# wristband2_ee459.net
KiCad netlist of a schematic drawn in Altium Designer
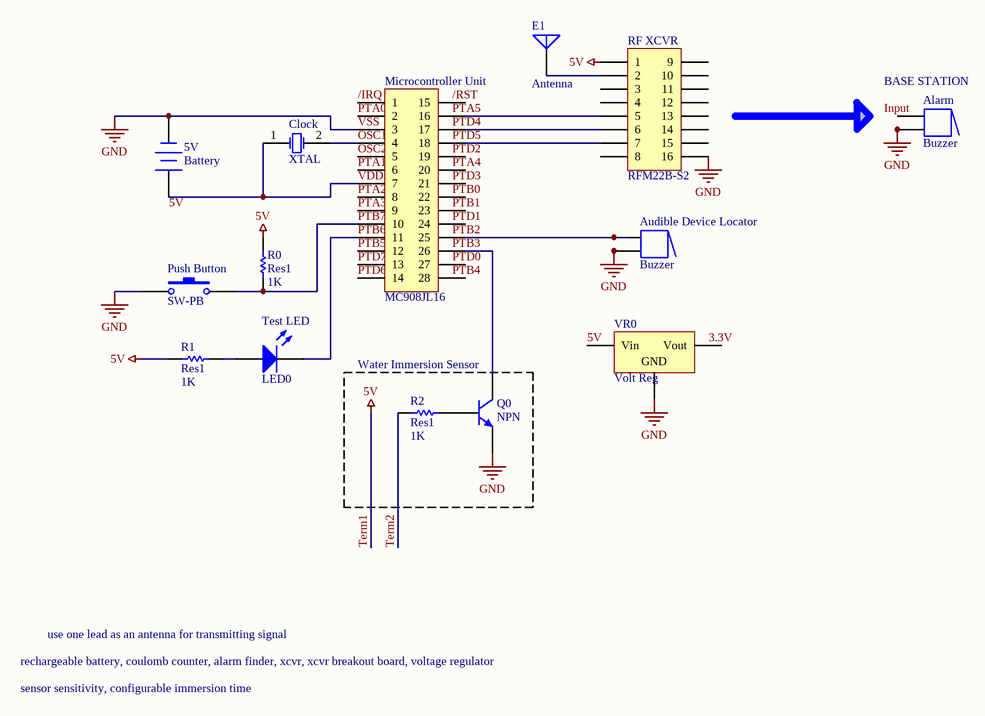
[diagram p0: wristband2_ee459.SchDoc]

(export (version "E")
  (design (tool "Eeschema 10.0.6"))
  (components
    (comp (ref "5V")
      (value "Battery")
      (footprint "BAT-2")
      (description "Multicell Battery")
      (fields (field (name "PUBLISHER") "Altium Limited"))
      (libsource (lib "Miscellaneous Devices") (part "Battery"))
    )
    (comp (ref "Alarm")
      (value "Buzzer")
      (footprint "ABSM-1574")
      (description "Magnetic Transducer Buzzer")
      (fields (field (name "PUBLISHER") "Altium Limited"))
      (libsource (lib "Miscellaneous Devices") (part "Buzzer"))
    )
    (comp (ref "Audible Device Locator")
      (value "Buzzer")
      (footprint "ABSM-1574")
      (description "Magnetic Transducer Buzzer")
      (fields (field (name "PUBLISHER") "Altium Limited"))
      (libsource (lib "Miscellaneous Devices") (part "Buzzer"))
    )
    (comp (ref "Clock")
      (value "XTAL")
      (footprint "R38")
      (description "Crystal Oscillator")
      (fields (field (name "PUBLISHER") "Altium Limited"))
      (libsource (lib "Miscellaneous Devices") (part "XTAL"))
    )
    (comp (ref "E1")
      (value "Antenna")
      (footprint "PIN1")
      (description "Generic Antenna")
      (fields (field (name "PUBLISHER") "Altium Limited"))
      (libsource (lib "Miscellaneous Devices") (part "Antenna"))
    )
    (comp (ref "Microcontroller Unit")
      (value "MC908JL16")
      (footprint "HDR2X14_CEN")
      (description "Header, 14-Pin, Dual row")
      (fields (field (name "PUBLISHER") "Altium Limited"))
      (libsource (lib "Miscellaneous Connectors") (part "Header 14X2A"))
    )
    (comp (ref "Push Button")
      (value "SW-PB")
      (footprint "SPST-2")
      (description "Switch")
      (fields (field (name "PUBLISHER") "Altium Limited"))
      (libsource (lib "Miscellaneous Devices") (part "SW-PB"))
    )
    (comp (ref "Q0")
      (value "NPN")
      (footprint "TO-226")
      (description "NPN Bipolar Transistor")
      (fields (field (name "PUBLISHER") "Altium Limited"))
      (libsource (lib "Miscellaneous Devices") (part "NPN"))
    )
    (comp (ref "R0")
      (value "Res1")
      (footprint "AXIAL-0.3")
      (description "Resistor")
      (fields (field (name "ALTIUM_VALUE") "1K") (field (name "PUBLISHER") "Altium Limited"))
      (libsource (lib "Miscellaneous Devices") (part "Res1"))
    )
    (comp (ref "R1")
      (value "Res1")
      (footprint "AXIAL-0.3")
      (description "Resistor")
      (fields (field (name "ALTIUM_VALUE") "1K") (field (name "PUBLISHER") "Altium Limited"))
      (libsource (lib "Miscellaneous Devices") (part "Res1"))
    )
    (comp (ref "R2")
      (value "Res1")
      (footprint "AXIAL-0.3")
      (description "Resistor")
      (fields (field (name "ALTIUM_VALUE") "1K") (field (name "PUBLISHER") "Altium Limited"))
      (libsource (lib "Miscellaneous Devices") (part "Res1"))
    )
    (comp (ref "RF XCVR")
      (value "RFM22B-S2")
      (footprint "HDR2X8_CEN")
      (description "Header, 8-Pin, Dual row")
      (fields (field (name "PUBLISHER") "Altium Limited"))
      (libsource (lib "Miscellaneous Connectors") (part "Header 8X2A"))
    )
    (comp (ref "Test LED")
      (value "LED0")
      (footprint "LED-0")
      (description "Typical INFRARED GaAs LED")
      (fields (field (name "PUBLISHER") "Altium Limited"))
      (libsource (lib "Miscellaneous Devices") (part "LED0"))
    )
    (comp (ref "VR0")
      (value "Volt Reg")
      (footprint "D2PAK")
      (description "Voltage Regulator")
      (fields (field (name "PUBLISHER") "Altium Limited"))
      (libsource (lib "Miscellaneous Devices") (part "Volt Reg"))
    )
  )
  (nets
    (net (code "3") (name "/OSC1") (class "Default")
      (node (ref "Clock") (pin "2") (pinfunction "OSC2_2") (pintype "passive"))
      (node (ref "Microcontroller Unit") (pin "4") (pinfunction "4_4") (pintype "passive"))
    )
    (net (code "4") (name "/OSC2") (class "Default")
      (node (ref "Microcontroller Unit") (pin "5") (pinfunction "5_5") (pintype "passive"))
    )
    (net (code "5") (name "/PTA0") (class "Default")
      (node (ref "Microcontroller Unit") (pin "2") (pinfunction "2_2") (pintype "passive"))
    )
    (net (code "6") (name "/PTA1") (class "Default")
      (node (ref "Microcontroller Unit") (pin "6") (pinfunction "6_6") (pintype "passive"))
    )
    (net (code "7") (name "/PTA2") (class "Default")
      (node (ref "Microcontroller Unit") (pin "8") (pinfunction "8_8") (pintype "passive"))
    )
    (net (code "8") (name "/PTA3") (class "Default")
      (node (ref "Microcontroller Unit") (pin "9") (pinfunction "9_9") (pintype "passive"))
    )
    (net (code "16") (name "/PTB5") (class "Default")
      (node (ref "Microcontroller Unit") (pin "12") (pinfunction "12_12") (pintype "passive"))
    )
    (net (code "17") (name "/PTB6") (class "Default")
      (node (ref "Microcontroller Unit") (pin "11") (pinfunction "11_11") (pintype "passive"))
      (node (ref "Test LED") (pin "2") (pinfunction "K_2") (pintype "passive"))
    )
    (net (code "18") (name "/PTB7") (class "Default")
      (node (ref "Microcontroller Unit") (pin "10") (pinfunction "10_10") (pintype "passive"))
      (node (ref "Push Button") (pin "2") (pinfunction "2_2") (pintype "passive"))
      (node (ref "R0") (pin "1") (pinfunction "1_1") (pintype "passive"))
    )
    (net (code "25") (name "/PTD6") (class "Default")
      (node (ref "Microcontroller Unit") (pin "14") (pinfunction "14_14") (pintype "passive"))
    )
    (net (code "26") (name "/PTD7") (class "Default")
      (node (ref "Microcontroller Unit") (pin "13") (pinfunction "13_13") (pintype "passive"))
    )
    (net (code "27") (name "/Term2") (class "Default")
      (node (ref "R2") (pin "1") (pinfunction "1_1") (pintype "passive"))
    )
    (net (code "28") (name "/VDD") (class "Default")
      (node (ref "5V") (pin "1") (pinfunction "+_1") (pintype "passive"))
      (node (ref "Clock") (pin "1") (pinfunction "OSC1_1") (pintype "passive"))
      (node (ref "Microcontroller Unit") (pin "7") (pinfunction "7_7") (pintype "passive"))
    )
    (net (code "29") (name "/{slash}IRQ") (class "Default")
      (node (ref "Microcontroller Unit") (pin "1") (pinfunction "1_1") (pintype "passive"))
    )
    (net (code "31") (name "5V") (class "Default")
      (node (ref "R0") (pin "2") (pinfunction "2_2") (pintype "passive"))
      (node (ref "R1") (pin "2") (pinfunction "2_2") (pintype "passive"))
      (node (ref "RF XCVR") (pin "1") (pinfunction "1_1") (pintype "passive"))
      (node (ref "VR0") (pin "1") (pinfunction "Vin_1") (pintype "passive"))
    )
    (net (code "32") (name "GND") (class "Default")
      (node (ref "5V") (pin "2") (pinfunction "-_2") (pintype "passive"))
      (node (ref "Alarm") (pin "2") (pinfunction "2_2") (pintype "passive"))
      (node (ref "Alarm") (pin "2A") (pinfunction "2A_2A") (pintype "passive"))
      (node (ref "Audible Device Locator") (pin "2") (pinfunction "2_2") (pintype "passive"))
      (node (ref "Audible Device Locator") (pin "2A") (pinfunction "2A_2A") (pintype "passive"))
      (node (ref "Microcontroller Unit") (pin "3") (pinfunction "3_3") (pintype "passive"))
      (node (ref "Push Button") (pin "1") (pinfunction "1_1") (pintype "passive"))
      (node (ref "Q0") (pin "3") (pinfunction "E_3") (pintype "passive"))
      (node (ref "RF XCVR") (pin "16") (pinfunction "16_16") (pintype "passive"))
      (node (ref "VR0") (pin "2") (pinfunction "GND_2") (pintype "passive"))
    )
    (net (code "33") (name "Net-(Alarm-Pad1)") (class "Default")
      (node (ref "Alarm") (pin "1") (pinfunction "1_1") (pintype "passive"))
      (node (ref "Alarm") (pin "1A") (pinfunction "1A_1A") (pintype "passive"))
    )
    (net (code "34") (name "Net-(Audible Device Locator-Pad1)") (class "Default")
      (node (ref "Audible Device Locator") (pin "1") (pinfunction "1_1") (pintype "passive"))
      (node (ref "Audible Device Locator") (pin "1A") (pinfunction "1A_1A") (pintype "passive"))
      (node (ref "Microcontroller Unit") (pin "25") (pinfunction "25_25") (pintype "passive"))
    )
    (net (code "35") (name "Net-(E1-A)") (class "Default")
      (node (ref "E1") (pin "1") (pinfunction "A_1") (pintype "passive"))
      (node (ref "RF XCVR") (pin "2") (pinfunction "2_2") (pintype "passive"))
    )
    (net (code "36") (name "Net-(Microcontroller Unit-Pad16)") (class "Default")
      (node (ref "Microcontroller Unit") (pin "16") (pinfunction "16_16") (pintype "passive"))
      (node (ref "RF XCVR") (pin "5") (pinfunction "5_5") (pintype "passive"))
    )
    (net (code "37") (name "Net-(Microcontroller Unit-Pad17)") (class "Default")
      (node (ref "Microcontroller Unit") (pin "17") (pinfunction "17_17") (pintype "passive"))
      (node (ref "RF XCVR") (pin "6") (pinfunction "6_6") (pintype "passive"))
    )
    (net (code "38") (name "Net-(Microcontroller Unit-Pad18)") (class "Default")
      (node (ref "Microcontroller Unit") (pin "18") (pinfunction "18_18") (pintype "passive"))
      (node (ref "RF XCVR") (pin "7") (pinfunction "7_7") (pintype "passive"))
    )
    (net (code "39") (name "Net-(Q0-B)") (class "Default")
      (node (ref "Q0") (pin "2") (pinfunction "B_2") (pintype "passive"))
      (node (ref "R2") (pin "2") (pinfunction "2_2") (pintype "passive"))
    )
    (net (code "40") (name "Net-(Q0-C)") (class "Default")
      (node (ref "Microcontroller Unit") (pin "26") (pinfunction "26_26") (pintype "passive"))
      (node (ref "Q0") (pin "1") (pinfunction "C_1") (pintype "passive"))
    )
    (net (code "41") (name "Net-(Test LED-A)") (class "Default")
      (node (ref "R1") (pin "1") (pinfunction "1_1") (pintype "passive"))
      (node (ref "Test LED") (pin "1") (pinfunction "A_1") (pintype "passive"))
    )
    (net (code "42") (name "unconnected-(Microcontroller Unit-Pad15)") (class "Default")
      (node (ref "Microcontroller Unit") (pin "15") (pinfunction "15_15") (pintype "passive"))
    )
    (net (code "43") (name "unconnected-(Microcontroller Unit-Pad19)") (class "Default")
      (node (ref "Microcontroller Unit") (pin "19") (pinfunction "19_19") (pintype "passive"))
    )
    (net (code "44") (name "unconnected-(Microcontroller Unit-Pad20)") (class "Default")
      (node (ref "Microcontroller Unit") (pin "20") (pinfunction "20_20") (pintype "passive"))
    )
    (net (code "45") (name "unconnected-(Microcontroller Unit-Pad21)") (class "Default")
      (node (ref "Microcontroller Unit") (pin "21") (pinfunction "21_21") (pintype "passive"))
    )
    (net (code "46") (name "unconnected-(Microcontroller Unit-Pad22)") (class "Default")
      (node (ref "Microcontroller Unit") (pin "22") (pinfunction "22_22") (pintype "passive"))
    )
    (net (code "47") (name "unconnected-(Microcontroller Unit-Pad23)") (class "Default")
      (node (ref "Microcontroller Unit") (pin "23") (pinfunction "23_23") (pintype "passive"))
    )
    (net (code "48") (name "unconnected-(Microcontroller Unit-Pad24)") (class "Default")
      (node (ref "Microcontroller Unit") (pin "24") (pinfunction "24_24") (pintype "passive"))
    )
    (net (code "49") (name "unconnected-(Microcontroller Unit-Pad27)") (class "Default")
      (node (ref "Microcontroller Unit") (pin "27") (pinfunction "27_27") (pintype "passive"))
    )
    (net (code "50") (name "unconnected-(Microcontroller Unit-Pad28)") (class "Default")
      (node (ref "Microcontroller Unit") (pin "28") (pinfunction "28_28") (pintype "passive"))
    )
    (net (code "51") (name "unconnected-(RF XCVR-Pad3)") (class "Default")
      (node (ref "RF XCVR") (pin "3") (pinfunction "3_3") (pintype "passive"))
    )
    (net (code "52") (name "unconnected-(RF XCVR-Pad4)") (class "Default")
      (node (ref "RF XCVR") (pin "4") (pinfunction "4_4") (pintype "passive"))
    )
    (net (code "53") (name "unconnected-(RF XCVR-Pad8)") (class "Default")
      (node (ref "RF XCVR") (pin "8") (pinfunction "8_8") (pintype "passive"))
    )
    (net (code "54") (name "unconnected-(RF XCVR-Pad9)") (class "Default")
      (node (ref "RF XCVR") (pin "9") (pinfunction "9_9") (pintype "passive"))
    )
    (net (code "55") (name "unconnected-(RF XCVR-Pad10)") (class "Default")
      (node (ref "RF XCVR") (pin "10") (pinfunction "10_10") (pintype "passive"))
    )
    (net (code "56") (name "unconnected-(RF XCVR-Pad11)") (class "Default")
      (node (ref "RF XCVR") (pin "11") (pinfunction "11_11") (pintype "passive"))
    )
    (net (code "57") (name "unconnected-(RF XCVR-Pad12)") (class "Default")
      (node (ref "RF XCVR") (pin "12") (pinfunction "12_12") (pintype "passive"))
    )
    (net (code "58") (name "unconnected-(RF XCVR-Pad13)") (class "Default")
      (node (ref "RF XCVR") (pin "13") (pinfunction "13_13") (pintype "passive"))
    )
    (net (code "59") (name "unconnected-(RF XCVR-Pad14)") (class "Default")
      (node (ref "RF XCVR") (pin "14") (pinfunction "14_14") (pintype "passive"))
    )
    (net (code "60") (name "unconnected-(RF XCVR-Pad15)") (class "Default")
      (node (ref "RF XCVR") (pin "15") (pinfunction "15_15") (pintype "passive"))
    )
    (net (code "61") (name "unconnected-(VR0-Vout-Pad3)") (class "Default")
      (node (ref "VR0") (pin "3") (pinfunction "Vout_3") (pintype "passive"))
    )
  )
)
